# power_board.net
KiCad netlist of a schematic drawn in Altium Designer
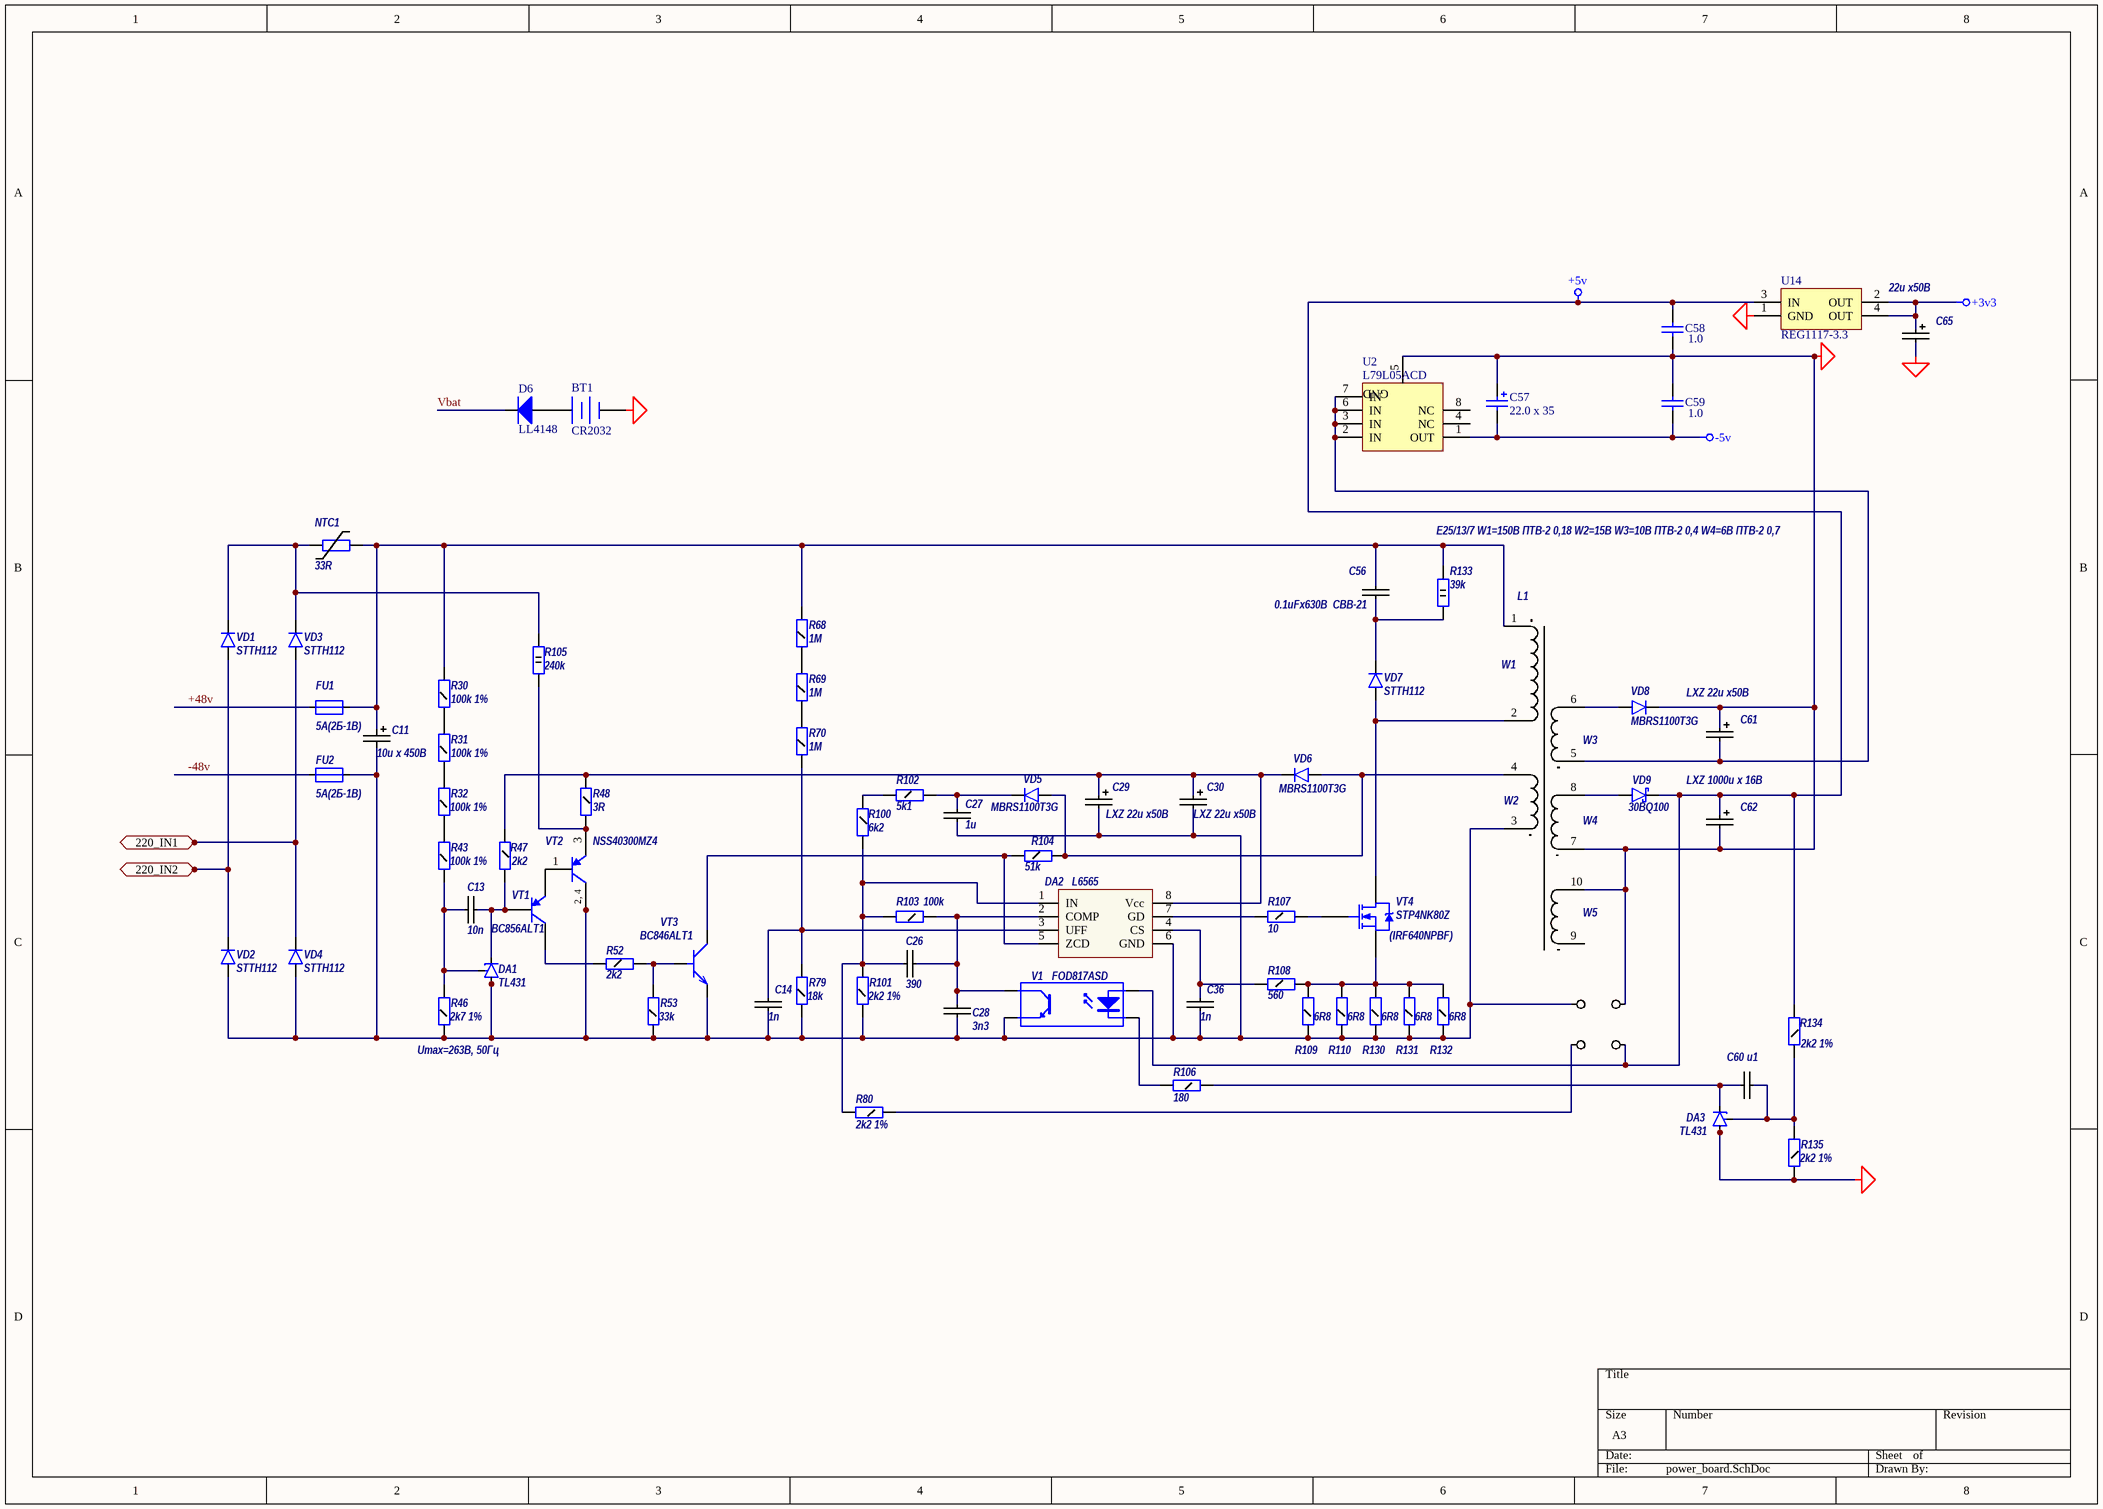
[diagram p0: power_board.SchDoc]

(export (version "E")
  (design (tool "Eeschema 10.0.6"))
  (components
    (comp (ref "BT1")
      (value "CR2032")
      (footprint "BAT_SUPP")
      (description "Multicell Battery")
      (fields (field (name "MANUFACTURER") "Generic Components") (field (name "PUBLISHER") "Altium Limited"))
      (libsource (lib "Miscellaneous Devices") (part "Battery"))
    )
    (comp (ref "C11")
      (value "10u x 450B")
      (footprint "10uf x 450V")
      (fields (field (name "POWER") "450В"))
      (libsource (lib "Common") (part "10мкФ х 450В"))
    )
    (comp (ref "C13")
      (value "10n")
      (footprint "_1206")
      (fields
        (field (name "TOLERANCE") "10%")
        (field (name "MANUFACTURERPARTNUMBER") "CC1206 1мкФ±10% 50В X7R")
      )
      (libsource (lib "igorenja") (part "Capacitor"))
    )
    (comp (ref "C14")
      (value "1n")
      (footprint "_1206")
      (fields (field (name "TOLERANCE") "10%"))
      (libsource (lib "Common") (part "Capacitor"))
    )
    (comp (ref "C26")
      (value "390")
      (footprint "_1206")
      (fields (field (name "TOLERANCE") "10%"))
      (libsource (lib "Common") (part "Capacitor"))
    )
    (comp (ref "C27")
      (value "1u")
      (footprint "_1206")
      (fields (field (name "TOLERANCE") "10%"))
      (libsource (lib "Common") (part "Capacitor"))
    )
    (comp (ref "C28")
      (value "3n3")
      (footprint "_1206")
      (fields (field (name "TOLERANCE") "10%"))
      (libsource (lib "Common") (part "Capacitor"))
    )
    (comp (ref "C29")
      (value "LXZ 22u x50B")
      (footprint "CAP_POL_6.3x12")
      (fields (field (name "TOLERANCE") "20%") (field (name "MANUFACTURERPARTNUMBER") "22мкФ±20% 50В KMF"))
      (libsource (lib "igorenja") (part "CAP_POL"))
    )
    (comp (ref "C30")
      (value "LXZ 22u x50B")
      (footprint "CAP_POL_6.3x12")
      (fields (field (name "TOLERANCE") "20%") (field (name "MANUFACTURERPARTNUMBER") "22мкФ±20% 50В KMF"))
      (libsource (lib "igorenja") (part "CAP_POL"))
    )
    (comp (ref "C36")
      (value "1n")
      (footprint "_1206")
      (fields (field (name "TOLERANCE") "10%"))
      (libsource (lib "Common") (part "Capacitor"))
    )
    (comp (ref "C56")
      (value "0.1uFx630B  CBB-21")
      (footprint "0.1uf *630V")
      (fields (field (name "TOLERANCE") "20%") (field (name "MANUFACTURERPARTNUMBER") "0.1мкФ±20% 250В"))
      (libsource (lib "igorenja") (part "Capacitor"))
    )
    (comp (ref "C57")
      (value "22.0 x 35")
      (footprint "el3")
      (description "Polarized Capacitor (Radial)")
      (fields (field (name "MANUFACTURER") "Generic Components") (field (name "PUBLISHER") "Altium Limited"))
      (libsource (lib "PAL") (part "Cap Pol1"))
    )
    (comp (ref "C58")
      (value "1.0")
      (footprint "C3216-1206")
      (description "Capacitor (Semiconductor SIM Model)")
      (fields (field (name "MANUFACTURER") "Generic Components") (field (name "PUBLISHER") "Altium Limited"))
      (libsource (lib "Miscellaneous Devices") (part "Cap Semi"))
    )
    (comp (ref "C59")
      (value "1.0")
      (footprint "C3216-1206")
      (description "Capacitor (Semiconductor SIM Model)")
      (fields (field (name "MANUFACTURER") "Generic Components") (field (name "PUBLISHER") "Altium Limited"))
      (libsource (lib "Miscellaneous Devices") (part "Cap Semi"))
    )
    (comp (ref "C60")
      (value "u1")
      (footprint "_1206")
      (fields (field (name "TOLERANCE") "10%"))
      (libsource (lib "Common") (part "Capacitor"))
    )
    (comp (ref "C61")
      (value "LXZ 22u x50B")
      (footprint "CAP_POL_6.3x12")
      (fields (field (name "TOLERANCE") "20%") (field (name "MANUFACTURERPARTNUMBER") "22мкФ±20% 50В KMF"))
      (libsource (lib "igorenja") (part "CAP_POL"))
    )
    (comp (ref "C62")
      (value "LXZ 1000u x 16B")
      (footprint "CAP_POL_13x21")
      (description "1000 мкФ х 25В")
      (fields (field (name "TOLERANCE") "-20 +80%"))
      (libsource (lib "Common") (part "1000 мкФ х 25В"))
    )
    (comp (ref "C65")
      (value "22u x50B")
      (footprint "CAP_POL_6.3x12")
      (fields (field (name "TOLERANCE") "20%") (field (name "MANUFACTURERPARTNUMBER") "22мкФ±20% 50В KMF"))
      (libsource (lib "igorenja") (part "CAP_POL"))
    )
    (comp (ref "D6")
      (value "LL4148")
      (footprint "_1206d")
      (description "Default Diode")
      (fields (field (name "MANUFACTURER") "Generic Components") (field (name "PUBLISHER") "Altium Limited"))
      (libsource (lib "PAL") (part "Diode"))
    )
    (comp (ref "DA1") (value "TL431") (footprint "SO-G8") (libsource (lib "igorenja") (part "TL431")))
    (comp (ref "DA2") (value "L6565") (footprint "SO-G8") (libsource (lib "Common") (part "L6565")))
    (comp (ref "DA3") (value "TL431") (footprint "SO-G8") (libsource (lib "Common") (part "TL431")))
    (comp (ref "FU1") (value "5A(2Б-1В)") (footprint "FUSE-3A") (libsource (lib "igorenja") (part "FUSE")))
    (comp (ref "FU2") (value "5A(2Б-1В)") (footprint "FUSE-3A") (libsource (lib "igorenja") (part "FUSE")))
    (comp (ref "L1")
      (value "E25/13/7 W1=150B ПТВ-2 0,18 W2=15B W3=10B ПТВ-2 0,4 W4=6B ПТВ-2 0,7")
      (footprint "Lps_360RH")
      (description "Индуктивность")
      (libsource (lib "Common") (part "Lps_360RH"))
    )
    (comp (ref "NTC1")
      (value "33R")
      (footprint "NTC 33R")
      (description "Позистор")
      (libsource (lib "Common") (part "NTC 33R"))
    )
    (comp (ref "R30")
      (value "100k 1%")
      (footprint "_1206")
      (description "R1206")
      (fields (field (name "TOLERANCE") "5%"))
      (libsource (lib "") (part "R1206_2"))
    )
    (comp (ref "R31")
      (value "100k 1%")
      (footprint "_1206")
      (description "R1206")
      (fields (field (name "TOLERANCE") "5%"))
      (libsource (lib "") (part "R1206_2"))
    )
    (comp (ref "R32")
      (value "100k 1%")
      (footprint "_1206")
      (description "R1206")
      (fields (field (name "TOLERANCE") "1%"))
      (libsource (lib "") (part "R1206_2"))
    )
    (comp (ref "R43")
      (value "100k 1%")
      (footprint "_1206")
      (description "R1206")
      (fields (field (name "TOLERANCE") "1%"))
      (libsource (lib "") (part "R1206_2"))
    )
    (comp (ref "R46")
      (value "2k7 1%")
      (footprint "_1206")
      (description "R1206")
      (fields (field (name "TOLERANCE") "1%"))
      (libsource (lib "") (part "R1206_2"))
    )
    (comp (ref "R47")
      (value "2k2")
      (footprint "_1206")
      (description "R1206")
      (fields (field (name "TOLERANCE") "1%"))
      (libsource (lib "Common") (part "R1206"))
    )
    (comp (ref "R48")
      (value "3R")
      (footprint "_1206")
      (description "R1206")
      (fields (field (name "TOLERANCE") "1%"))
      (libsource (lib "Common") (part "R1206"))
    )
    (comp (ref "R52")
      (value "2k2")
      (footprint "_1206")
      (description "R1206")
      (fields (field (name "TOLERANCE") "1%"))
      (libsource (lib "") (part "R1206_1"))
    )
    (comp (ref "R53")
      (value "33k")
      (footprint "_1206")
      (description "R1206")
      (fields (field (name "TOLERANCE") "1%"))
      (libsource (lib "") (part "R1206_2"))
    )
    (comp (ref "R68")
      (value "1M")
      (footprint "_1206")
      (description "R1206")
      (fields (field (name "TOLERANCE") "5%"))
      (libsource (lib "") (part "R1206_2"))
    )
    (comp (ref "R69")
      (value "1M")
      (footprint "_1206")
      (description "R1206")
      (fields (field (name "TOLERANCE") "5%"))
      (libsource (lib "") (part "R1206_2"))
    )
    (comp (ref "R70")
      (value "1M")
      (footprint "_1206")
      (description "R1206")
      (fields (field (name "TOLERANCE") "1%"))
      (libsource (lib "") (part "R1206_2"))
    )
    (comp (ref "R79")
      (value "18k")
      (footprint "_1206")
      (description "R1206")
      (fields (field (name "TOLERANCE") "1%"))
      (libsource (lib "") (part "R1206_2"))
    )
    (comp (ref "R80")
      (value "2k2 1%")
      (footprint "_1206")
      (description "R1206")
      (fields (field (name "TOLERANCE") "1%"))
      (libsource (lib "") (part "R1206_3"))
    )
    (comp (ref "R100")
      (value "6k2")
      (footprint "_1206")
      (description "R1206")
      (fields (field (name "TOLERANCE") "1%"))
      (libsource (lib "Common") (part "R1206"))
    )
    (comp (ref "R101")
      (value "2k2 1%")
      (footprint "_1206")
      (description "R1206")
      (fields (field (name "TOLERANCE") "1%"))
      (libsource (lib "") (part "R1206_2"))
    )
    (comp (ref "R102")
      (value "5k1")
      (footprint "_1206")
      (description "R1206")
      (fields (field (name "TOLERANCE") "1%"))
      (libsource (lib "") (part "R1206_1"))
    )
    (comp (ref "R103")
      (value "100k")
      (footprint "_1206")
      (description "R1206")
      (fields (field (name "TOLERANCE") "1%"))
      (libsource (lib "") (part "R1206_3"))
    )
    (comp (ref "R104")
      (value "51k")
      (footprint "_1206")
      (description "R1206")
      (fields (field (name "TOLERANCE") "5%"))
      (libsource (lib "") (part "R1206_1"))
    )
    (comp (ref "R105")
      (value "240k")
      (footprint "MF-2 vert")
      (fields (field (name "TOLERANCE") "10%"))
      (libsource (lib "") (part "Res 2W_1"))
    )
    (comp (ref "R106")
      (value "180")
      (footprint "_1206")
      (description "R1206")
      (fields (field (name "TOLERANCE") "1%"))
      (libsource (lib "") (part "R1206_3"))
    )
    (comp (ref "R107")
      (value "10")
      (footprint "_1206")
      (description "R1206")
      (fields (field (name "TOLERANCE") "5%"))
      (libsource (lib "") (part "R1206_1"))
    )
    (comp (ref "R108")
      (value "560")
      (footprint "_1206")
      (description "R1206")
      (fields (field (name "TOLERANCE") "5%"))
      (libsource (lib "") (part "R1206_1"))
    )
    (comp (ref "R109")
      (value "6R8")
      (footprint "_1206")
      (description "R1206")
      (fields (field (name "TOLERANCE") "5%"))
      (libsource (lib "") (part "R1206_2"))
    )
    (comp (ref "R110")
      (value "6R8")
      (footprint "_1206")
      (description "R1206")
      (fields (field (name "TOLERANCE") "5%"))
      (libsource (lib "") (part "R1206_2"))
    )
    (comp (ref "R130")
      (value "6R8")
      (footprint "_1206")
      (description "R1206")
      (fields (field (name "TOLERANCE") "5%"))
      (libsource (lib "") (part "R1206_2"))
    )
    (comp (ref "R131")
      (value "6R8")
      (footprint "_1206")
      (description "R1206")
      (fields (field (name "TOLERANCE") "5%"))
      (libsource (lib "") (part "R1206_2"))
    )
    (comp (ref "R132")
      (value "6R8")
      (footprint "_1206")
      (description "R1206")
      (fields (field (name "TOLERANCE") "5%"))
      (libsource (lib "") (part "R1206_2"))
    )
    (comp (ref "R133") (value "39k") (footprint "MF-2 vert") (libsource (lib "Common") (part "Res 2W")))
    (comp (ref "R134")
      (value "2k2 1%")
      (footprint "_1206")
      (description "R1206")
      (fields (field (name "TOLERANCE") "1%"))
      (libsource (lib "") (part "R1206_1"))
    )
    (comp (ref "R135")
      (value "2k2 1%")
      (footprint "_1206")
      (description "R1206")
      (fields (field (name "TOLERANCE") "1%"))
      (libsource (lib "") (part "R1206_1"))
    )
    (comp (ref "U2")
      (value "L79L05ACD")
      (footprint "SO-G8")
      (description "Negative Voltage Regulator")
      (fields (field (name "MANUFACTURER") "ST-Microelectronics") (field (name "PUBLISHER") "Altium Limited"))
      (libsource (lib "ST Power Mgt Voltage Regulator") (part "L79L05ACD"))
    )
    (comp (ref "U14")
      (value "REG1117-3.3")
      (footprint "SIP-G3/C7.4")
      (description "800mA and 1A Low Dropout Positive Regulator 2.85V, 3.3V, 5V, and Adjustable")
      (fields (field (name "MANUFACTURER") "Burr-Brown") (field (name "PUBLISHER") "Altium Limited"))
      (libsource (lib "BB Power Mgt Voltage Regulator") (part "REG1117-3.3"))
    )
    (comp (ref "V1")
      (value "FOD817ASD")
      (footprint "FOD817ASD")
      (libsource (lib "Common") (part "FOD817ASD"))
    )
    (comp (ref "VD1")
      (value "STTH112")
      (footprint "10bq*")
      (fields (field (name "MANUFACTURERPARTNUMBER") "STTH2R060U"))
      (libsource (lib "IVERTORSICH") (part "DIOD_2"))
    )
    (comp (ref "VD2")
      (value "STTH112")
      (footprint "10bq*")
      (fields (field (name "MANUFACTURERPARTNUMBER") "STTH2R060U"))
      (libsource (lib "IVERTORSICH") (part "DIOD_2"))
    )
    (comp (ref "VD3")
      (value "STTH112")
      (footprint "10bq*")
      (fields (field (name "MANUFACTURERPARTNUMBER") "STTH2R060U"))
      (libsource (lib "IVERTORSICH") (part "DIOD_2"))
    )
    (comp (ref "VD4")
      (value "STTH112")
      (footprint "10bq*")
      (fields (field (name "MANUFACTURERPARTNUMBER") "STTH2R060U"))
      (libsource (lib "IVERTORSICH") (part "DIOD_2"))
    )
    (comp (ref "VD5") (value "MBRS1100T3G") (footprint "10bq*") (libsource (lib "Common") (part "DIOD_1")))
    (comp (ref "VD6") (value "MBRS1100T3G") (footprint "10bq*") (libsource (lib "Common") (part "DIOD_1")))
    (comp (ref "VD7")
      (value "STTH112")
      (footprint "10bq*")
      (fields (field (name "MANUFACTURERPARTNUMBER") "STTH2R060U"))
      (libsource (lib "IVERTORSICH") (part "DIOD_2"))
    )
    (comp (ref "VD8") (value "MBRS1100T3G") (footprint "10bq*") (libsource (lib "Common") (part "DIOD_1")))
    (comp (ref "VD9") (value "30BQ100") (footprint "30bq*") (libsource (lib "igorenja") (part "DIOD_SH")))
    (comp (ref "VT1")
      (value "BC856ALT1")
      (footprint "318-08")
      (description "General Purpose Transistor PNP Silicon")
      (fields (field (name "MANUFACTURER") "ON Semiconductor") (field (name "PUBLISHER") "Altium Limited"))
      (libsource (lib "Common") (part "BC856ALT1"))
    )
    (comp (ref "VT2")
      (value "NSS40300MZ4")
      (footprint "SOT223_N")
      (description "Транзистор")
      (fields (field (name "PUBLISHER") "Altium Limited"))
      (libsource (lib "Philips Discrete BJT - Medium Power") (part "BSP32"))
    )
    (comp (ref "VT3")
      (value "BC846ALT1")
      (footprint "SOT-23")
      (libsource (lib "igorenja") (part "TRANS_npn"))
    )
    (comp (ref "VT4")
      (value "STP4NK80Z")
      (footprint "TO-220AB")
      (description "N-Channel Power MOSFET")
      (fields (field (name "PUBLISHER") "Altium Limited"))
      (libsource (lib "Miscellaneous Devices") (part "NMOS-2"))
    )
    (comp (ref "XP1") (value "PAD") (footprint "PAD_otv") (libsource (lib "Common") (part "PAD")))
    (comp (ref "XP2") (value "PAD") (footprint "PAD_otv") (libsource (lib "Common") (part "PAD")))
    (comp (ref "XP3") (value "PAD") (footprint "PAD_otv") (libsource (lib "Common") (part "PAD")))
    (comp (ref "XP4") (value "PAD") (footprint "PAD_otv") (libsource (lib "Common") (part "PAD")))
    (comp (ref "XP5") (value "PAD") (footprint "PAD_otv") (libsource (lib "Common") (part "PAD")))
    (comp (ref "XP6") (value "PAD") (footprint "PAD_otv") (libsource (lib "Common") (part "PAD")))
  )
  (nets
    (net (code "1") (name "+3v3") (class "Default")
      (node (ref "C65") (pin "+") (pintype "passive"))
      (node (ref "U14") (pin "2") (pinfunction "OUT_2") (pintype "power_in"))
      (node (ref "U14") (pin "4") (pinfunction "OUT_4") (pintype "power_in"))
    )
    (net (code "2") (name "+5v") (class "Default")
      (node (ref "C58") (pin "2") (pinfunction "2_2") (pintype "passive"))
      (node (ref "C62") (pin "+") (pintype "passive"))
      (node (ref "R134") (pin "2") (pinfunction "2_2") (pintype "passive"))
      (node (ref "U14") (pin "3") (pinfunction "IN_3") (pintype "power_in"))
      (node (ref "V1") (pin "1") (pinfunction "A_1") (pintype "passive"))
      (node (ref "VD9") (pin "2") (pintype "passive"))
      (node (ref "XP6") (pin "1") (pintype "passive"))
    )
    (net (code "3") (name "-5v") (class "Default")
      (node (ref "C57") (pin "2") (pinfunction "2_2") (pintype "passive"))
      (node (ref "C59") (pin "1") (pinfunction "1_1") (pintype "passive"))
      (node (ref "U2") (pin "1") (pinfunction "OUT_1") (pintype "power_in"))
    )
    (net (code "4") (name "/+48v") (class "Default")
      (node (ref "FU1") (pin "1") (pinfunction "0_1") (pintype "passive"))
    )
    (net (code "5") (name "/-48v") (class "Default")
      (node (ref "FU2") (pin "1") (pinfunction "0_1") (pintype "passive"))
    )
    (net (code "6") (name "/220_IN1") (class "Default")
      (node (ref "VD3") (pin "1") (pintype "passive"))
      (node (ref "VD4") (pin "2") (pintype "passive"))
      (node (ref "XP1") (pin "1") (pintype "passive"))
    )
    (net (code "7") (name "/220_IN2") (class "Default")
      (node (ref "VD1") (pin "1") (pintype "passive"))
      (node (ref "VD2") (pin "2") (pintype "passive"))
      (node (ref "XP2") (pin "1") (pintype "passive"))
    )
    (net (code "8") (name "/Vbat") (class "Default")
      (node (ref "D6") (pin "2") (pinfunction "K_2") (pintype "passive"))
    )
    (net (code "9") (name "GND") (class "Default")
      (node (ref "BT1") (pin "2") (pinfunction "-_2") (pintype "passive"))
      (node (ref "C57") (pin "1") (pinfunction "1_1") (pintype "passive"))
      (node (ref "C58") (pin "1") (pinfunction "1_1") (pintype "passive"))
      (node (ref "C59") (pin "2") (pinfunction "2_2") (pintype "passive"))
      (node (ref "C61") (pin "+") (pintype "passive"))
      (node (ref "C62") (pin "-") (pintype "passive"))
      (node (ref "C65") (pin "-") (pintype "passive"))
      (node (ref "DA3") (pin "6") (pintype "passive"))
      (node (ref "DA3") (pin "7") (pintype "passive"))
      (node (ref "L1") (pin "10") (pintype "passive"))
      (node (ref "L1") (pin "7") (pintype "passive"))
      (node (ref "R135") (pin "1") (pinfunction "1_1") (pintype "passive"))
      (node (ref "U14") (pin "1") (pinfunction "GND_1") (pintype "power_in"))
      (node (ref "U2") (pin "5") (pinfunction "GND_5") (pintype "power_in"))
      (node (ref "VD8") (pin "2") (pintype "passive"))
      (node (ref "XP5") (pin "1") (pintype "passive"))
    )
    (net (code "10") (name "Net-(BT1-+)") (class "Default")
      (node (ref "BT1") (pin "1") (pinfunction "+_1") (pintype "passive"))
      (node (ref "D6") (pin "1") (pinfunction "A_1") (pintype "passive"))
    )
    (net (code "11") (name "Net-(C13-OA-Pad1)") (class "Default")
      (node (ref "C13") (pin "1") (pinfunction "OA_1") (pintype "passive"))
      (node (ref "DA1") (pin "8") (pintype "passive"))
      (node (ref "R43") (pin "1") (pinfunction "1_1") (pintype "passive"))
      (node (ref "R46") (pin "2") (pinfunction "2_2") (pintype "passive"))
    )
    (net (code "12") (name "Net-(C27-OA-Pad1)") (class "Default")
      (node (ref "C27") (pin "1") (pinfunction "OA_1") (pintype "passive"))
      (node (ref "R102") (pin "2") (pinfunction "2_2") (pintype "passive"))
      (node (ref "VD5") (pin "2") (pintype "passive"))
    )
    (net (code "13") (name "Net-(C56-OA-Pad2)") (class "Default")
      (node (ref "C56") (pin "2") (pinfunction "OA_2") (pintype "passive"))
      (node (ref "R133") (pin "1") (pinfunction "1_1") (pintype "passive"))
      (node (ref "VD7") (pin "2") (pintype "passive"))
    )
    (net (code "14") (name "Net-(C60-OA-Pad1)") (class "Default")
      (node (ref "C60") (pin "1") (pinfunction "OA_1") (pintype "passive"))
      (node (ref "DA3") (pin "1") (pintype "passive"))
      (node (ref "R106") (pin "1") (pinfunction "1_1") (pintype "passive"))
    )
    (net (code "15") (name "Net-(C60-OA-Pad2)") (class "Default")
      (node (ref "C60") (pin "2") (pinfunction "OA_2") (pintype "passive"))
      (node (ref "DA3") (pin "8") (pintype "passive"))
      (node (ref "R134") (pin "1") (pinfunction "1_1") (pintype "passive"))
      (node (ref "R135") (pin "2") (pinfunction "2_2") (pintype "passive"))
    )
    (net (code "16") (name "Net-(C61-Pad-)") (class "Default")
      (node (ref "C61") (pin "-") (pintype "passive"))
      (node (ref "L1") (pin "5") (pintype "passive"))
      (node (ref "U2") (pin "2") (pinfunction "IN_2") (pintype "power_in"))
      (node (ref "U2") (pin "3") (pinfunction "IN_3") (pintype "power_in"))
      (node (ref "U2") (pin "6") (pinfunction "IN_6") (pintype "power_in"))
      (node (ref "U2") (pin "7") (pinfunction "IN_7") (pintype "power_in"))
    )
    (net (code "17") (name "Net-(DA2-COMP)") (class "Default")
      (node (ref "C26") (pin "2") (pinfunction "OA_2") (pintype "passive"))
      (node (ref "C28") (pin "2") (pinfunction "OA_2") (pintype "passive"))
      (node (ref "DA2") (pin "2") (pinfunction "COMP_2") (pintype "passive"))
      (node (ref "R103") (pin "1") (pinfunction "1_1") (pintype "passive"))
      (node (ref "V1") (pin "4") (pinfunction "C_4") (pintype "passive"))
    )
    (net (code "18") (name "Net-(DA2-CS)") (class "Default")
      (node (ref "C36") (pin "1") (pinfunction "OA_1") (pintype "passive"))
      (node (ref "DA2") (pin "4") (pinfunction "CS_4") (pintype "passive"))
      (node (ref "R108") (pin "1") (pinfunction "1_1") (pintype "passive"))
    )
    (net (code "19") (name "Net-(DA2-GD)") (class "Default")
      (node (ref "DA2") (pin "7") (pinfunction "GD_7") (pintype "passive"))
      (node (ref "R107") (pin "1") (pinfunction "1_1") (pintype "passive"))
    )
    (net (code "20") (name "Net-(DA2-GND)") (class "Default")
      (node (ref "C11") (pin "2") (pintype "passive"))
      (node (ref "C14") (pin "2") (pinfunction "OA_2") (pintype "passive"))
      (node (ref "C27") (pin "2") (pinfunction "OA_2") (pintype "passive"))
      (node (ref "C28") (pin "1") (pinfunction "OA_1") (pintype "passive"))
      (node (ref "C29") (pin "-") (pintype "passive"))
      (node (ref "C30") (pin "-") (pintype "passive"))
      (node (ref "C36") (pin "2") (pinfunction "OA_2") (pintype "passive"))
      (node (ref "DA1") (pin "6") (pintype "passive"))
      (node (ref "DA1") (pin "7") (pintype "passive"))
      (node (ref "DA2") (pin "6") (pinfunction "GND_6") (pintype "passive"))
      (node (ref "FU2") (pin "2") (pinfunction "1_2") (pintype "passive"))
      (node (ref "L1") (pin "3") (pintype "passive"))
      (node (ref "R101") (pin "1") (pinfunction "1_1") (pintype "passive"))
      (node (ref "R109") (pin "1") (pinfunction "1_1") (pintype "passive"))
      (node (ref "R110") (pin "1") (pinfunction "1_1") (pintype "passive"))
      (node (ref "R130") (pin "1") (pinfunction "1_1") (pintype "passive"))
      (node (ref "R131") (pin "1") (pinfunction "1_1") (pintype "passive"))
      (node (ref "R132") (pin "1") (pinfunction "1_1") (pintype "passive"))
      (node (ref "R46") (pin "1") (pinfunction "1_1") (pintype "passive"))
      (node (ref "R53") (pin "1") (pinfunction "1_1") (pintype "passive"))
      (node (ref "R79") (pin "1") (pinfunction "1_1") (pintype "passive"))
      (node (ref "V1") (pin "3") (pinfunction "E_3") (pintype "passive"))
      (node (ref "VD2") (pin "1") (pintype "passive"))
      (node (ref "VD4") (pin "1") (pintype "passive"))
      (node (ref "VT2") (pin "2") (pinfunction "C_2") (pintype "passive"))
      (node (ref "VT2") (pin "4") (pinfunction "C_4") (pintype "passive"))
      (node (ref "VT3") (pin "2") (pintype "passive"))
      (node (ref "XP3") (pin "1") (pintype "passive"))
    )
    (net (code "21") (name "Net-(DA2-IN)") (class "Default")
      (node (ref "C26") (pin "1") (pinfunction "OA_1") (pintype "passive"))
      (node (ref "DA2") (pin "1") (pinfunction "IN_1") (pintype "passive"))
      (node (ref "R100") (pin "2") (pinfunction "2_2") (pintype "passive"))
      (node (ref "R101") (pin "2") (pinfunction "2_2") (pintype "passive"))
      (node (ref "R103") (pin "2") (pinfunction "2_2") (pintype "passive"))
      (node (ref "R80") (pin "2") (pinfunction "2_2") (pintype "passive"))
    )
    (net (code "22") (name "Net-(DA2-UFF)") (class "Default")
      (node (ref "C14") (pin "1") (pinfunction "OA_1") (pintype "passive"))
      (node (ref "DA2") (pin "3") (pinfunction "UFF_3") (pintype "passive"))
      (node (ref "R70") (pin "1") (pinfunction "1_1") (pintype "passive"))
      (node (ref "R79") (pin "2") (pinfunction "2_2") (pintype "passive"))
    )
    (net (code "23") (name "Net-(DA2-Vcc)") (class "Default")
      (node (ref "C29") (pin "+") (pintype "passive"))
      (node (ref "C30") (pin "+") (pintype "passive"))
      (node (ref "DA2") (pin "8") (pinfunction "Vcc_8") (pintype "passive"))
      (node (ref "R47") (pin "1") (pinfunction "1_1") (pintype "passive"))
      (node (ref "R48") (pin "1") (pinfunction "1_1") (pintype "passive"))
      (node (ref "VD6") (pin "2") (pintype "passive"))
    )
    (net (code "24") (name "Net-(DA2-ZCD)") (class "Default")
      (node (ref "DA2") (pin "5") (pinfunction "ZCD_5") (pintype "passive"))
      (node (ref "R104") (pin "1") (pinfunction "1_1") (pintype "passive"))
      (node (ref "VT3") (pin "3") (pintype "passive"))
    )
    (net (code "25") (name "Net-(FU1-1)") (class "Default")
      (node (ref "C11") (pin "1") (pintype "passive"))
      (node (ref "C56") (pin "1") (pinfunction "OA_1") (pintype "passive"))
      (node (ref "FU1") (pin "2") (pinfunction "1_2") (pintype "passive"))
      (node (ref "L1") (pin "1") (pintype "passive"))
      (node (ref "NTC1") (pin "2") (pinfunction "2_2") (pintype "passive"))
      (node (ref "R133") (pin "2") (pinfunction "2_2") (pintype "passive"))
      (node (ref "R30") (pin "2") (pinfunction "2_2") (pintype "passive"))
      (node (ref "R68") (pin "2") (pinfunction "2_2") (pintype "passive"))
    )
    (net (code "26") (name "Net-(L1-Pad4)") (class "Default")
      (node (ref "L1") (pin "4") (pintype "passive"))
      (node (ref "R104") (pin "2") (pinfunction "2_2") (pintype "passive"))
      (node (ref "VD5") (pin "1") (pintype "passive"))
      (node (ref "VD6") (pin "1") (pintype "passive"))
    )
    (net (code "27") (name "Net-(L1-Pad6)") (class "Default")
      (node (ref "L1") (pin "6") (pintype "passive"))
      (node (ref "VD8") (pin "1") (pintype "passive"))
    )
    (net (code "28") (name "Net-(L1-Pad8)") (class "Default")
      (node (ref "L1") (pin "8") (pintype "passive"))
      (node (ref "VD9") (pin "1") (pintype "passive"))
    )
    (net (code "29") (name "Net-(NTC1-Pad1)") (class "Default")
      (node (ref "NTC1") (pin "1") (pinfunction "1_1") (pintype "passive"))
      (node (ref "R105") (pin "1") (pinfunction "1_1") (pintype "passive"))
      (node (ref "VD1") (pin "2") (pintype "passive"))
      (node (ref "VD3") (pin "2") (pintype "passive"))
    )
    (net (code "30") (name "Net-(R30-Pad1)") (class "Default")
      (node (ref "R30") (pin "1") (pinfunction "1_1") (pintype "passive"))
      (node (ref "R31") (pin "2") (pinfunction "2_2") (pintype "passive"))
    )
    (net (code "31") (name "Net-(R31-Pad1)") (class "Default")
      (node (ref "R31") (pin "1") (pinfunction "1_1") (pintype "passive"))
      (node (ref "R32") (pin "2") (pinfunction "2_2") (pintype "passive"))
    )
    (net (code "32") (name "Net-(R32-Pad1)") (class "Default")
      (node (ref "R32") (pin "1") (pinfunction "1_1") (pintype "passive"))
      (node (ref "R43") (pin "2") (pinfunction "2_2") (pintype "passive"))
    )
    (net (code "33") (name "Net-(R52-Pad2)") (class "Default")
      (node (ref "R52") (pin "2") (pinfunction "2_2") (pintype "passive"))
      (node (ref "R53") (pin "2") (pinfunction "2_2") (pintype "passive"))
      (node (ref "VT3") (pin "1") (pintype "passive"))
    )
    (net (code "34") (name "Net-(R68-Pad1)") (class "Default")
      (node (ref "R68") (pin "1") (pinfunction "1_1") (pintype "passive"))
      (node (ref "R69") (pin "2") (pinfunction "2_2") (pintype "passive"))
    )
    (net (code "35") (name "Net-(R69-Pad1)") (class "Default")
      (node (ref "R69") (pin "1") (pinfunction "1_1") (pintype "passive"))
      (node (ref "R70") (pin "2") (pinfunction "2_2") (pintype "passive"))
    )
    (net (code "36") (name "Net-(R80-Pad1)") (class "Default")
      (node (ref "R80") (pin "1") (pinfunction "1_1") (pintype "passive"))
      (node (ref "XP4") (pin "1") (pintype "passive"))
    )
    (net (code "37") (name "Net-(R100-Pad1)") (class "Default")
      (node (ref "R100") (pin "1") (pinfunction "1_1") (pintype "passive"))
      (node (ref "R102") (pin "1") (pinfunction "1_1") (pintype "passive"))
    )
    (net (code "38") (name "Net-(V1-K)") (class "Default")
      (node (ref "R106") (pin "2") (pinfunction "2_2") (pintype "passive"))
      (node (ref "V1") (pin "2") (pinfunction "K_2") (pintype "passive"))
    )
    (net (code "39") (name "Net-(VT1-B)") (class "Default")
      (node (ref "C13") (pin "2") (pinfunction "OA_2") (pintype "passive"))
      (node (ref "DA1") (pin "1") (pintype "passive"))
      (node (ref "R47") (pin "2") (pinfunction "2_2") (pintype "passive"))
      (node (ref "VT1") (pin "1") (pinfunction "B_1") (pintype "passive"))
    )
    (net (code "40") (name "Net-(VT1-C)") (class "Default")
      (node (ref "R52") (pin "1") (pinfunction "1_1") (pintype "passive"))
      (node (ref "VT1") (pin "3") (pinfunction "C_3") (pintype "passive"))
    )
    (net (code "41") (name "Net-(VT1-E)") (class "Default")
      (node (ref "VT1") (pin "2") (pinfunction "E_2") (pintype "passive"))
      (node (ref "VT2") (pin "1") (pinfunction "B_1") (pintype "passive"))
    )
    (net (code "42") (name "Net-(VT2-E)") (class "Default")
      (node (ref "R105") (pin "2") (pinfunction "2_2") (pintype "passive"))
      (node (ref "R48") (pin "2") (pinfunction "2_2") (pintype "passive"))
      (node (ref "VT2") (pin "3") (pinfunction "E_3") (pintype "passive"))
    )
    (net (code "43") (name "Net-(VT4-D)") (class "Default")
      (node (ref "L1") (pin "2") (pintype "passive"))
      (node (ref "VD7") (pin "1") (pintype "passive"))
      (node (ref "VT4") (pin "2") (pinfunction "D_2") (pintype "passive"))
    )
    (net (code "44") (name "Net-(VT4-G)") (class "Default")
      (node (ref "R107") (pin "2") (pinfunction "2_2") (pintype "passive"))
      (node (ref "VT4") (pin "1") (pinfunction "G_1") (pintype "passive"))
    )
    (net (code "45") (name "Net-(VT4-S)") (class "Default")
      (node (ref "R108") (pin "2") (pinfunction "2_2") (pintype "passive"))
      (node (ref "R109") (pin "2") (pinfunction "2_2") (pintype "passive"))
      (node (ref "R110") (pin "2") (pinfunction "2_2") (pintype "passive"))
      (node (ref "R130") (pin "2") (pinfunction "2_2") (pintype "passive"))
      (node (ref "R131") (pin "2") (pinfunction "2_2") (pintype "passive"))
      (node (ref "R132") (pin "2") (pinfunction "2_2") (pintype "passive"))
      (node (ref "VT4") (pin "3") (pinfunction "S_3") (pintype "passive"))
    )
    (net (code "46") (name "unconnected-(L1-Pad9)") (class "Default")
      (node (ref "L1") (pin "9") (pintype "passive"))
    )
    (net (code "47") (name "unconnected-(U2-NC-Pad4)") (class "Default")
      (node (ref "U2") (pin "4") (pinfunction "NC_4") (pintype "passive"))
    )
    (net (code "48") (name "unconnected-(U2-NC-Pad8)") (class "Default")
      (node (ref "U2") (pin "8") (pinfunction "NC_8") (pintype "passive"))
    )
  )
)
